# M_D_ext_power-solar.net
KiCad netlist of a schematic drawn in EAGLE
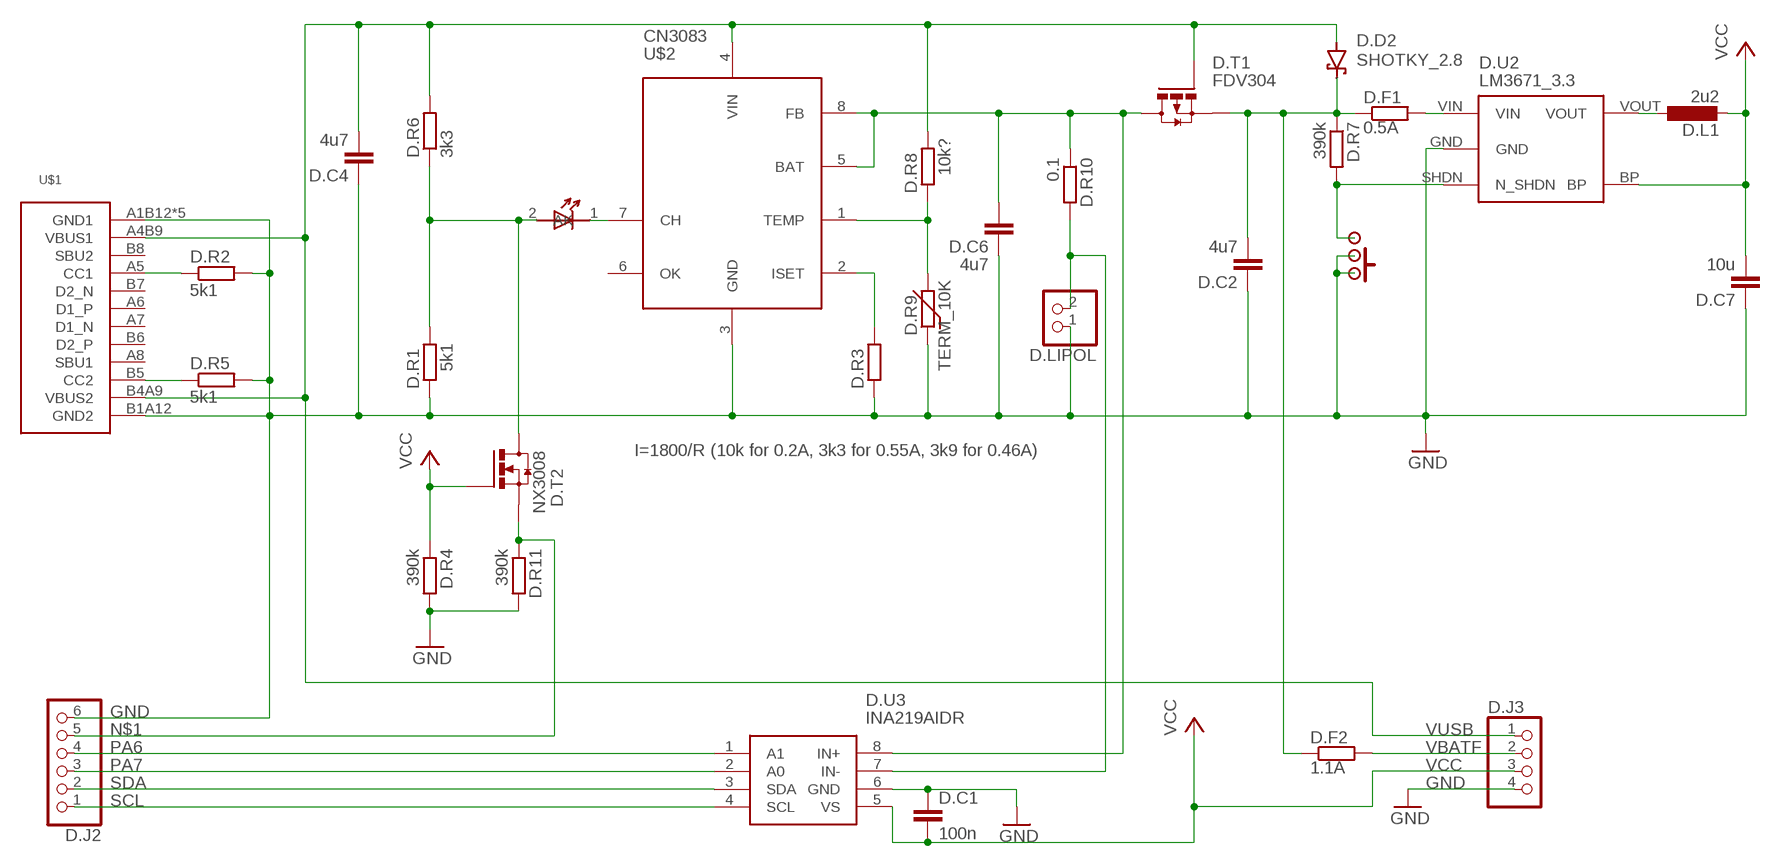
[diagram p0: schematic, sheet 1]

(export (version "E")
  (design (tool "Eeschema 10.0.6"))
  (components
    (comp (ref "D.C1")
      (value "100n")
      (footprint "eagle-import:C0603")
      (libsource (lib "eagle-import") (part "C-EUC0603"))
    )
    (comp (ref "D.C2")
      (value "4u7")
      (footprint "eagle-import:C0603")
      (libsource (lib "eagle-import") (part "C-EUC0603"))
    )
    (comp (ref "D.C4")
      (value "4u7")
      (footprint "eagle-import:C0603")
      (libsource (lib "eagle-import") (part "C-EUC0603"))
    )
    (comp (ref "D.C6")
      (value "4u7")
      (footprint "eagle-import:C0603")
      (libsource (lib "eagle-import") (part "C-EUC0603"))
    )
    (comp (ref "D.C7")
      (value "10u")
      (footprint "eagle-import:C0805")
      (libsource (lib "eagle-import") (part "C-EUC0805"))
    )
    (comp (ref "D.D1")
      (value "LED_1.8")
      (footprint "eagle-import:LED_1.8")
      (libsource (lib "eagle-import") (part "LED_1.8"))
    )
    (comp (ref "D.D2")
      (value "SHOTKY_2.8")
      (footprint "eagle-import:SHOTKY_2.8")
      (libsource (lib "eagle-import") (part "SHOTKY_2.8"))
    )
    (comp (ref "D.F1")
      (value "0.5A")
      (footprint "eagle-import:R0805")
      (libsource (lib "eagle-import") (part "R-EU_R0805"))
    )
    (comp (ref "D.F2")
      (value "1.1A")
      (footprint "eagle-import:R0805")
      (libsource (lib "eagle-import") (part "R-EU_R0805"))
    )
    (comp (ref "D.J2")
      (value "PINHD-1X6")
      (footprint "eagle-import:1X06")
      (libsource (lib "eagle-import") (part "PINHD-1X6"))
    )
    (comp (ref "D.J3")
      (value "PINHD-1X4")
      (footprint "eagle-import:1X04")
      (libsource (lib "eagle-import") (part "PINHD-1X4"))
    )
    (comp (ref "D.L1")
      (value "2u2")
      (footprint "eagle-import:L3230M")
      (libsource (lib "eagle-import") (part "L-EUL3230M"))
    )
    (comp (ref "D.LIPOL")
      (value "PINHD-1X21X2-2")
      (footprint "eagle-import:1X02-2")
      (libsource (lib "eagle-import") (part "PINHD-1X21X2-2"))
    )
    (comp (ref "D.ON/OFF/RESET")
      (value "SWITCH")
      (footprint "eagle-import:SWITCH")
      (libsource (lib "eagle-import") (part "SWITCH"))
    )
    (comp (ref "D.R1")
      (value "5k1")
      (footprint "eagle-import:R0603")
      (libsource (lib "eagle-import") (part "R-EU_R0603"))
    )
    (comp (ref "D.R2")
      (value "5k1")
      (footprint "eagle-import:R0603")
      (libsource (lib "eagle-import") (part "R-EU_R0603"))
    )
    (comp (ref "D.R3")
      (value "I=1800/R (10k for 0.2A, 3k3 for 0.55A, 3k9 for 0.46A)")
      (footprint "eagle-import:R0603")
      (libsource (lib "eagle-import") (part "R-EU_R0603"))
    )
    (comp (ref "D.R4")
      (value "390k")
      (footprint "eagle-import:R0603")
      (libsource (lib "eagle-import") (part "R-EU_R0603"))
    )
    (comp (ref "D.R5")
      (value "5k1")
      (footprint "eagle-import:R0603")
      (libsource (lib "eagle-import") (part "R-EU_R0603"))
    )
    (comp (ref "D.R6")
      (value "3k3")
      (footprint "eagle-import:R0603")
      (libsource (lib "eagle-import") (part "R-EU_R0603"))
    )
    (comp (ref "D.R7")
      (value "390k")
      (footprint "eagle-import:R0603")
      (libsource (lib "eagle-import") (part "R-EU_R0603"))
    )
    (comp (ref "D.R8")
      (value "10k?")
      (footprint "eagle-import:R0603")
      (libsource (lib "eagle-import") (part "R-EU_R0603"))
    )
    (comp (ref "D.R9")
      (value "TERM_10K")
      (footprint "eagle-import:THERM")
      (libsource (lib "eagle-import") (part "THERM"))
    )
    (comp (ref "D.R10")
      (value "0.1")
      (footprint "eagle-import:R0805")
      (libsource (lib "eagle-import") (part "R-EU_R0805"))
    )
    (comp (ref "D.R11")
      (value "390k")
      (footprint "eagle-import:R0603")
      (libsource (lib "eagle-import") (part "R-EU_R0603"))
    )
    (comp (ref "D.T1")
      (value "FDV304")
      (footprint "eagle-import:SO23")
      (libsource (lib "eagle-import") (part "P-MOSFET"))
    )
    (comp (ref "D.T2")
      (value "NX3008")
      (footprint "eagle-import:SO23")
      (libsource (lib "eagle-import") (part "N-MOSFET"))
    )
    (comp (ref "D.U2")
      (value "LM3671_3.3")
      (footprint "eagle-import:SOT32-5")
      (libsource (lib "eagle-import") (part "STABILISER_APE8865"))
    )
    (comp (ref "D.U3")
      (value "INA219AIDR")
      (footprint "eagle-import:SOIC127P600X175-8N")
      (fields (field (name "MOUSER_PART_NUMBER") "595-INA219AIDR"))
      (libsource (lib "eagle-import") (part "INA219AIDR"))
    )
    (comp (ref "U$1")
      (value "USB-C")
      (footprint "eagle-import:USB-C")
      (libsource (lib "eagle-import") (part "USB-C"))
    )
    (comp (ref "U$2")
      (value "CN3083")
      (footprint "eagle-import:SOP8")
      (libsource (lib "eagle-import") (part "CN3083"))
    )
  )
  (nets
    (net (code "1") (name "/N$1") (class "Default")
      (node (ref "D.J2") (pin "5") (pinfunction "5_5") (pintype "passive"))
      (node (ref "D.R11") (pin "1") (pinfunction "1_1") (pintype "passive"))
      (node (ref "D.T2") (pin "S") (pinfunction "S_S") (pintype "passive"))
    )
    (net (code "2") (name "/PA6") (class "Default")
      (node (ref "D.J2") (pin "4") (pinfunction "4_4") (pintype "passive"))
      (node (ref "D.U3") (pin "1") (pinfunction "A1_1") (pintype "bidirectional"))
    )
    (net (code "3") (name "/PA7") (class "Default")
      (node (ref "D.J2") (pin "3") (pinfunction "3_3") (pintype "passive"))
      (node (ref "D.U3") (pin "2") (pinfunction "A0_2") (pintype "bidirectional"))
    )
    (net (code "4") (name "/SCL") (class "Default")
      (node (ref "D.J2") (pin "1") (pinfunction "1_1") (pintype "passive"))
      (node (ref "D.U3") (pin "4") (pinfunction "SCL_4") (pintype "bidirectional"))
    )
    (net (code "5") (name "/SDA") (class "Default")
      (node (ref "D.J2") (pin "2") (pinfunction "2_2") (pintype "passive"))
      (node (ref "D.U3") (pin "3") (pinfunction "SDA_3") (pintype "bidirectional"))
    )
    (net (code "6") (name "/VBATF") (class "Default")
      (node (ref "D.F2") (pin "2") (pinfunction "2_2") (pintype "passive"))
      (node (ref "D.J3") (pin "2") (pinfunction "2_2") (pintype "passive"))
    )
    (net (code "7") (name "/VUSB") (class "Default")
      (node (ref "D.C4") (pin "2") (pinfunction "2_2") (pintype "passive"))
      (node (ref "D.D2") (pin "A") (pinfunction "A_A") (pintype "passive"))
      (node (ref "D.J3") (pin "1") (pinfunction "1_1") (pintype "passive"))
      (node (ref "D.R6") (pin "2") (pinfunction "2_2") (pintype "passive"))
      (node (ref "D.R8") (pin "2") (pinfunction "2_2") (pintype "passive"))
      (node (ref "D.T1") (pin "G") (pinfunction "G_G") (pintype "passive"))
      (node (ref "U$1") (pin "A4B9") (pinfunction "VBUS1_A4B9") (pintype "bidirectional"))
      (node (ref "U$1") (pin "B4A9") (pinfunction "VBUS2_B4A9") (pintype "bidirectional"))
      (node (ref "U$2") (pin "4") (pinfunction "VIN_4") (pintype "bidirectional"))
    )
    (net (code "8") (name "GND") (class "Default")
      (node (ref "D.C1") (pin "1") (pinfunction "1_1") (pintype "passive"))
      (node (ref "D.C2") (pin "1") (pinfunction "1_1") (pintype "passive"))
      (node (ref "D.C4") (pin "1") (pinfunction "1_1") (pintype "passive"))
      (node (ref "D.C6") (pin "1") (pinfunction "1_1") (pintype "passive"))
      (node (ref "D.C7") (pin "1") (pinfunction "1_1") (pintype "passive"))
      (node (ref "D.J2") (pin "6") (pinfunction "6_6") (pintype "passive"))
      (node (ref "D.J3") (pin "4") (pinfunction "4_4") (pintype "passive"))
      (node (ref "D.LIPOL") (pin "1") (pinfunction "1_1") (pintype "passive"))
      (node (ref "D.ON/OFF/RESET") (pin "P$1") (pinfunction "P$1_P$1") (pintype "bidirectional"))
      (node (ref "D.ON/OFF/RESET") (pin "P$2") (pinfunction "P$2_P$2") (pintype "bidirectional"))
      (node (ref "D.ON/OFF/RESET") (pin "P$4") (pinfunction "P$1_P$4") (pintype "bidirectional"))
      (node (ref "D.R1") (pin "1") (pinfunction "1_1") (pintype "passive"))
      (node (ref "D.R11") (pin "2") (pinfunction "2_2") (pintype "passive"))
      (node (ref "D.R2") (pin "2") (pinfunction "2_2") (pintype "passive"))
      (node (ref "D.R3") (pin "1") (pinfunction "1_1") (pintype "passive"))
      (node (ref "D.R4") (pin "2") (pinfunction "2_2") (pintype "passive"))
      (node (ref "D.R5") (pin "2") (pinfunction "2_2") (pintype "passive"))
      (node (ref "D.R9") (pin "1") (pinfunction "1_1") (pintype "passive"))
      (node (ref "D.U2") (pin "GND") (pinfunction "GND_GND") (pintype "bidirectional"))
      (node (ref "D.U3") (pin "6") (pinfunction "GND_6") (pintype "bidirectional"))
      (node (ref "U$1") (pin "A1B12") (pinfunction "GND1_A1B12") (pintype "bidirectional"))
      (node (ref "U$1") (pin "B1A12") (pinfunction "GND2_B1A12") (pintype "bidirectional"))
      (node (ref "U$1") (pin "SH1") (pinfunction "GND1_SH1") (pintype "bidirectional"))
      (node (ref "U$1") (pin "SH2") (pinfunction "GND1_SH2") (pintype "bidirectional"))
      (node (ref "U$1") (pin "SH3") (pinfunction "GND1_SH3") (pintype "bidirectional"))
      (node (ref "U$1") (pin "SH4") (pinfunction "GND1_SH4") (pintype "bidirectional"))
      (node (ref "U$2") (pin "3") (pinfunction "GND_3") (pintype "bidirectional"))
    )
    (net (code "9") (name "Net-(D.D1-A)") (class "Default")
      (node (ref "D.D1") (pin "2") (pinfunction "A_2") (pintype "bidirectional"))
      (node (ref "D.R1") (pin "2") (pinfunction "2_2") (pintype "passive"))
      (node (ref "D.R6") (pin "1") (pinfunction "1_1") (pintype "passive"))
      (node (ref "D.T2") (pin "D") (pinfunction "D_D") (pintype "passive"))
    )
    (net (code "10") (name "Net-(D.D1-K)") (class "Default")
      (node (ref "D.D1") (pin "1") (pinfunction "K_1") (pintype "bidirectional"))
      (node (ref "U$2") (pin "7") (pinfunction "CH_7") (pintype "bidirectional"))
    )
    (net (code "11") (name "Net-(D.D2-C)") (class "Default")
      (node (ref "D.C2") (pin "2") (pinfunction "2_2") (pintype "passive"))
      (node (ref "D.D2") (pin "K") (pinfunction "C_K") (pintype "passive"))
      (node (ref "D.F1") (pin "1") (pinfunction "1_1") (pintype "passive"))
      (node (ref "D.F2") (pin "1") (pinfunction "1_1") (pintype "passive"))
      (node (ref "D.R7") (pin "1") (pinfunction "1_1") (pintype "passive"))
      (node (ref "D.T1") (pin "S") (pinfunction "S_S") (pintype "passive"))
    )
    (net (code "12") (name "Net-(D.F1-Pad2)") (class "Default")
      (node (ref "D.F1") (pin "2") (pinfunction "2_2") (pintype "passive"))
      (node (ref "D.U2") (pin "VIN") (pinfunction "VIN_VIN") (pintype "bidirectional"))
    )
    (net (code "13") (name "Net-(D.L1-Pad1)") (class "Default")
      (node (ref "D.L1") (pin "1") (pinfunction "1_1") (pintype "passive"))
      (node (ref "D.U2") (pin "VOUT") (pinfunction "VOUT_VOUT") (pintype "bidirectional"))
    )
    (net (code "14") (name "Net-(D.U2-N_SHDN)") (class "Default")
      (node (ref "D.ON/OFF/RESET") (pin "P$3") (pinfunction "P$3_P$3") (pintype "bidirectional"))
      (node (ref "D.ON/OFF/RESET") (pin "P$5") (pinfunction "P$3_P$5") (pintype "bidirectional"))
      (node (ref "D.R7") (pin "2") (pinfunction "2_2") (pintype "passive"))
      (node (ref "D.U2") (pin "SHDN") (pinfunction "N_SHDN_SHDN") (pintype "bidirectional"))
    )
    (net (code "15") (name "Net-(D.U3-IN+)") (class "Default")
      (node (ref "D.C6") (pin "2") (pinfunction "2_2") (pintype "passive"))
      (node (ref "D.R10") (pin "1") (pinfunction "1_1") (pintype "passive"))
      (node (ref "D.T1") (pin "D") (pinfunction "D_D") (pintype "passive"))
      (node (ref "D.U3") (pin "8") (pinfunction "IN+_8") (pintype "bidirectional"))
      (node (ref "U$2") (pin "5") (pinfunction "BAT_5") (pintype "bidirectional"))
      (node (ref "U$2") (pin "8") (pinfunction "FB_8") (pintype "bidirectional"))
    )
    (net (code "16") (name "Net-(D.U3-IN-)") (class "Default")
      (node (ref "D.LIPOL") (pin "2") (pinfunction "2_2") (pintype "passive"))
      (node (ref "D.R10") (pin "2") (pinfunction "2_2") (pintype "passive"))
      (node (ref "D.U3") (pin "7") (pinfunction "IN-_7") (pintype "bidirectional"))
    )
    (net (code "17") (name "Net-(U$1-CC1)") (class "Default")
      (node (ref "D.R2") (pin "1") (pinfunction "1_1") (pintype "passive"))
      (node (ref "U$1") (pin "A5") (pinfunction "CC1_A5") (pintype "bidirectional"))
    )
    (net (code "18") (name "Net-(U$1-CC2)") (class "Default")
      (node (ref "D.R5") (pin "1") (pinfunction "1_1") (pintype "passive"))
      (node (ref "U$1") (pin "B5") (pinfunction "CC2_B5") (pintype "bidirectional"))
    )
    (net (code "19") (name "Net-(U$2-ISET)") (class "Default")
      (node (ref "D.R3") (pin "2") (pinfunction "2_2") (pintype "passive"))
      (node (ref "U$2") (pin "2") (pinfunction "ISET_2") (pintype "bidirectional"))
    )
    (net (code "20") (name "Net-(U$2-TEMP)") (class "Default")
      (node (ref "D.R8") (pin "1") (pinfunction "1_1") (pintype "passive"))
      (node (ref "D.R9") (pin "2") (pinfunction "2_2") (pintype "passive"))
      (node (ref "U$2") (pin "1") (pinfunction "TEMP_1") (pintype "bidirectional"))
    )
    (net (code "21") (name "VCC") (class "Default")
      (node (ref "D.C1") (pin "2") (pinfunction "2_2") (pintype "passive"))
      (node (ref "D.C7") (pin "2") (pinfunction "2_2") (pintype "passive"))
      (node (ref "D.J3") (pin "3") (pinfunction "3_3") (pintype "passive"))
      (node (ref "D.L1") (pin "2") (pinfunction "2_2") (pintype "passive"))
      (node (ref "D.R4") (pin "1") (pinfunction "1_1") (pintype "passive"))
      (node (ref "D.T2") (pin "G") (pinfunction "G_G") (pintype "passive"))
      (node (ref "D.U2") (pin "BP") (pinfunction "BP_BP") (pintype "bidirectional"))
      (node (ref "D.U3") (pin "5") (pinfunction "VS_5") (pintype "bidirectional"))
    )
    (net (code "22") (name "unconnected-(U$1-D1_N-PadA7)") (class "Default")
      (node (ref "U$1") (pin "A7") (pinfunction "D1_N_A7") (pintype "bidirectional"))
    )
    (net (code "23") (name "unconnected-(U$1-D1_P-PadA6)") (class "Default")
      (node (ref "U$1") (pin "A6") (pinfunction "D1_P_A6") (pintype "bidirectional"))
    )
    (net (code "24") (name "unconnected-(U$1-D2_N-PadB7)") (class "Default")
      (node (ref "U$1") (pin "B7") (pinfunction "D2_N_B7") (pintype "bidirectional"))
    )
    (net (code "25") (name "unconnected-(U$1-D2_P-PadB6)") (class "Default")
      (node (ref "U$1") (pin "B6") (pinfunction "D2_P_B6") (pintype "bidirectional"))
    )
    (net (code "26") (name "unconnected-(U$1-SBU1-PadA8)") (class "Default")
      (node (ref "U$1") (pin "A8") (pinfunction "SBU1_A8") (pintype "bidirectional"))
    )
    (net (code "27") (name "unconnected-(U$1-SBU2-PadB8)") (class "Default")
      (node (ref "U$1") (pin "B8") (pinfunction "SBU2_B8") (pintype "bidirectional"))
    )
    (net (code "28") (name "unconnected-(U$2-OK-Pad6)") (class "Default")
      (node (ref "U$2") (pin "6") (pinfunction "OK_6") (pintype "bidirectional"))
    )
  )
)
